# COMBLE.net
KiCad netlist of a schematic drawn in Altium Designer
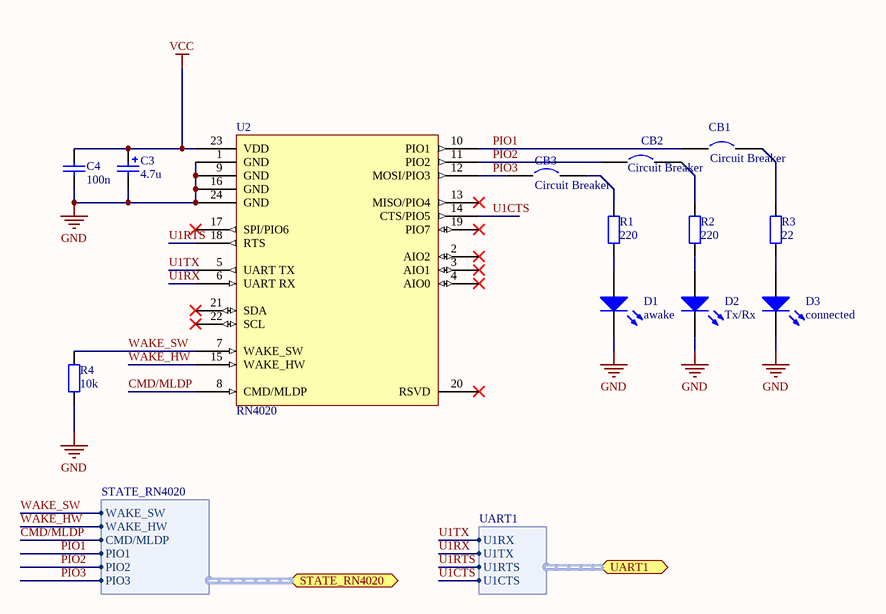
[diagram p0: COMBLE.SchDoc]

(export (version "E")
  (design (tool "Eeschema 10.0.6"))
  (components
    (comp (ref "C3")
      (value "4.7u")
      (footprint "CAP POL 1206/3216 - 1.2MM")
      (description "Condensateur tantale CMS, 4.7 µF, 10 V, Série T491, ± 10%")
      (libsource (lib "Miscellaneous Devices") (part "Cap Pol2"))
    )
    (comp (ref "C4")
      (value "100n")
      (footprint "RES 0603/1608")
      (libsource (lib "Miscellaneous Devices") (part "Cap"))
    )
    (comp (ref "CB1")
      (value "Circuit Breaker")
      (footprint "JUMPER PAD")
      (libsource (lib "Miscellaneous Devices") (part "Circuit Breaker"))
    )
    (comp (ref "CB2")
      (value "Circuit Breaker")
      (footprint "JUMPER PAD")
      (libsource (lib "Miscellaneous Devices") (part "Circuit Breaker"))
    )
    (comp (ref "CB3")
      (value "Circuit Breaker")
      (footprint "JUMPER PAD")
      (libsource (lib "Miscellaneous Devices") (part "Circuit Breaker"))
    )
    (comp (ref "D1")
      (value "awake")
      (footprint "LED 0603/1608 BLUE")
      (description "LED, Ambre, CMS, 0.8mm x 1.1mm, 5 mA, 1.95 V, 590 nm")
      (libsource (lib "Miscellaneous Devices") (part "LED2"))
    )
    (comp (ref "D2")
      (value "Tx/Rx")
      (footprint "LED 0603/1608 BLUE")
      (description "LED, Ambre, CMS, 0.8mm x 1.1mm, 5 mA, 1.95 V, 590 nm")
      (libsource (lib "Miscellaneous Devices") (part "LED2"))
    )
    (comp (ref "D3")
      (value "connected")
      (footprint "LED 0603/1608 BLUE")
      (description "LED, Bleu, CMS, 0.8mm x 1.6mm, 5 mA, 2.9 V, 470 nm")
      (libsource (lib "Miscellaneous Devices") (part "LED2"))
    )
    (comp (ref "R1")
      (value "220")
      (footprint "RES 0603/1608")
      (libsource (lib "Miscellaneous Devices") (part "Res2"))
    )
    (comp (ref "R2")
      (value "220")
      (footprint "RES 0603/1608")
      (libsource (lib "Miscellaneous Devices") (part "Res2"))
    )
    (comp (ref "R3")
      (value "22")
      (footprint "RES 0603/1608")
      (libsource (lib "Miscellaneous Devices") (part "Res2"))
    )
    (comp (ref "R4")
      (value "10k")
      (footprint "RES 0603/1608")
      (description "Résistance à puce CMS, Couche épaisse, 10 kohm, 150 V, 0805")
      (libsource (lib "") (part "Res2_1"))
    )
    (comp (ref "U2")
      (value "RN4020")
      (footprint "RN4020")
      (description "MICROCHIP  RN4020-V/RM  Module Bluetooth® Low Energy v4.1, 2.4GHz à 2.48GHz, 1 MBPS")
      (libsource (lib "ComponentLib") (part "RN4020"))
    )
  )
  (nets
    (net (code "3") (name "/CMD{slash}MLDP") (class "Default")
      (node (ref "U2") (pin "8") (pinfunction "CMD/MLDP_8") (pintype "input"))
    )
    (net (code "4") (name "/PIO1") (class "Default")
      (node (ref "CB1") (pin "1") (pinfunction "1_1") (pintype "passive"))
      (node (ref "U2") (pin "10") (pinfunction "PIO1_10") (pintype "output"))
    )
    (net (code "5") (name "/PIO2") (class "Default")
      (node (ref "CB2") (pin "1") (pinfunction "1_1") (pintype "passive"))
      (node (ref "U2") (pin "11") (pinfunction "PIO2_11") (pintype "output"))
    )
    (net (code "6") (name "/PIO3") (class "Default")
      (node (ref "CB3") (pin "1") (pinfunction "1_1") (pintype "passive"))
      (node (ref "U2") (pin "12") (pinfunction "MOSI/PIO3_12") (pintype "output"))
    )
    (net (code "7") (name "/U1CTS") (class "Default")
      (node (ref "U2") (pin "14") (pinfunction "CTS/PIO5_14") (pintype "output"))
    )
    (net (code "8") (name "/U1RTS") (class "Default")
      (node (ref "U2") (pin "18") (pinfunction "RTS_18") (pintype "output"))
    )
    (net (code "9") (name "/U1RX") (class "Default")
      (node (ref "U2") (pin "6") (pinfunction "UART_RX_6") (pintype "input"))
    )
    (net (code "10") (name "/U1TX") (class "Default")
      (node (ref "U2") (pin "5") (pinfunction "UART_TX_5") (pintype "output"))
    )
    (net (code "11") (name "/WAKE_HW") (class "Default")
      (node (ref "U2") (pin "15") (pinfunction "WAKE_HW_15") (pintype "input"))
    )
    (net (code "12") (name "/WAKE_SW") (class "Default")
      (node (ref "R4") (pin "1") (pinfunction "1_1") (pintype "passive"))
      (node (ref "U2") (pin "7") (pinfunction "WAKE_SW_7") (pintype "input"))
    )
    (net (code "15") (name "GND") (class "Default")
      (node (ref "C3") (pin "2") (pinfunction "2_2") (pintype "passive"))
      (node (ref "C4") (pin "2") (pinfunction "2_2") (pintype "passive"))
      (node (ref "D1") (pin "2") (pinfunction "K_2") (pintype "passive"))
      (node (ref "D2") (pin "2") (pinfunction "K_2") (pintype "passive"))
      (node (ref "D3") (pin "2") (pinfunction "K_2") (pintype "passive"))
      (node (ref "R4") (pin "2") (pinfunction "2_2") (pintype "passive"))
      (node (ref "U2") (pin "1") (pinfunction "GND_1") (pintype "power_in"))
      (node (ref "U2") (pin "16") (pinfunction "GND_16") (pintype "power_in"))
      (node (ref "U2") (pin "24") (pinfunction "GND_24") (pintype "power_in"))
      (node (ref "U2") (pin "9") (pinfunction "GND_9") (pintype "power_in"))
    )
    (net (code "16") (name "Net-(CB1-Pad2)") (class "Default")
      (node (ref "CB1") (pin "2") (pinfunction "2_2") (pintype "passive"))
      (node (ref "R3") (pin "2") (pinfunction "2_2") (pintype "passive"))
    )
    (net (code "17") (name "Net-(CB2-Pad2)") (class "Default")
      (node (ref "CB2") (pin "2") (pinfunction "2_2") (pintype "passive"))
      (node (ref "R2") (pin "2") (pinfunction "2_2") (pintype "passive"))
    )
    (net (code "18") (name "Net-(CB3-Pad2)") (class "Default")
      (node (ref "CB3") (pin "2") (pinfunction "2_2") (pintype "passive"))
      (node (ref "R1") (pin "2") (pinfunction "2_2") (pintype "passive"))
    )
    (net (code "19") (name "Net-(D1-A)") (class "Default")
      (node (ref "D1") (pin "1") (pinfunction "A_1") (pintype "passive"))
      (node (ref "R1") (pin "1") (pinfunction "1_1") (pintype "passive"))
    )
    (net (code "20") (name "Net-(D2-A)") (class "Default")
      (node (ref "D2") (pin "1") (pinfunction "A_1") (pintype "passive"))
      (node (ref "R2") (pin "1") (pinfunction "1_1") (pintype "passive"))
    )
    (net (code "21") (name "Net-(D3-A)") (class "Default")
      (node (ref "D3") (pin "1") (pinfunction "A_1") (pintype "passive"))
      (node (ref "R3") (pin "1") (pinfunction "1_1") (pintype "passive"))
    )
    (net (code "22") (name "VCC") (class "Default")
      (node (ref "C3") (pin "1") (pinfunction "1_1") (pintype "passive"))
      (node (ref "C4") (pin "1") (pinfunction "1_1") (pintype "passive"))
      (node (ref "U2") (pin "23") (pinfunction "VDD_23") (pintype "power_in"))
    )
    (net (code "23") (name "unconnected-(U2-AIO0-Pad4)") (class "Default")
      (node (ref "U2") (pin "4") (pinfunction "AIO0_4") (pintype "bidirectional+no_connect"))
    )
    (net (code "24") (name "unconnected-(U2-AIO1-Pad3)") (class "Default")
      (node (ref "U2") (pin "3") (pinfunction "AIO1_3") (pintype "bidirectional+no_connect"))
    )
    (net (code "25") (name "unconnected-(U2-AIO2-Pad2)") (class "Default")
      (node (ref "U2") (pin "2") (pinfunction "AIO2_2") (pintype "bidirectional+no_connect"))
    )
    (net (code "26") (name "unconnected-(U2-MISO{slash}PIO4-Pad13)") (class "Default")
      (node (ref "U2") (pin "13") (pinfunction "MISO/PIO4_13") (pintype "output+no_connect"))
    )
    (net (code "27") (name "unconnected-(U2-PIO7-Pad19)") (class "Default")
      (node (ref "U2") (pin "19") (pinfunction "PIO7_19") (pintype "bidirectional+no_connect"))
    )
    (net (code "28") (name "unconnected-(U2-RSVD-Pad20)") (class "Default")
      (node (ref "U2") (pin "20") (pinfunction "RSVD_20") (pintype "passive+no_connect"))
    )
    (net (code "29") (name "unconnected-(U2-SCL-Pad22)") (class "Default")
      (node (ref "U2") (pin "22") (pinfunction "SCL_22") (pintype "bidirectional+no_connect"))
    )
    (net (code "30") (name "unconnected-(U2-SDA-Pad21)") (class "Default")
      (node (ref "U2") (pin "21") (pinfunction "SDA_21") (pintype "bidirectional+no_connect"))
    )
    (net (code "31") (name "unconnected-(U2-SPI{slash}PIO6-Pad17)") (class "Default")
      (node (ref "U2") (pin "17") (pinfunction "SPI/PIO6_17") (pintype "output+no_connect"))
    )
  )
)
